# OpenBook_Schematic_v40.net
KiCad netlist of a schematic drawn in EAGLE
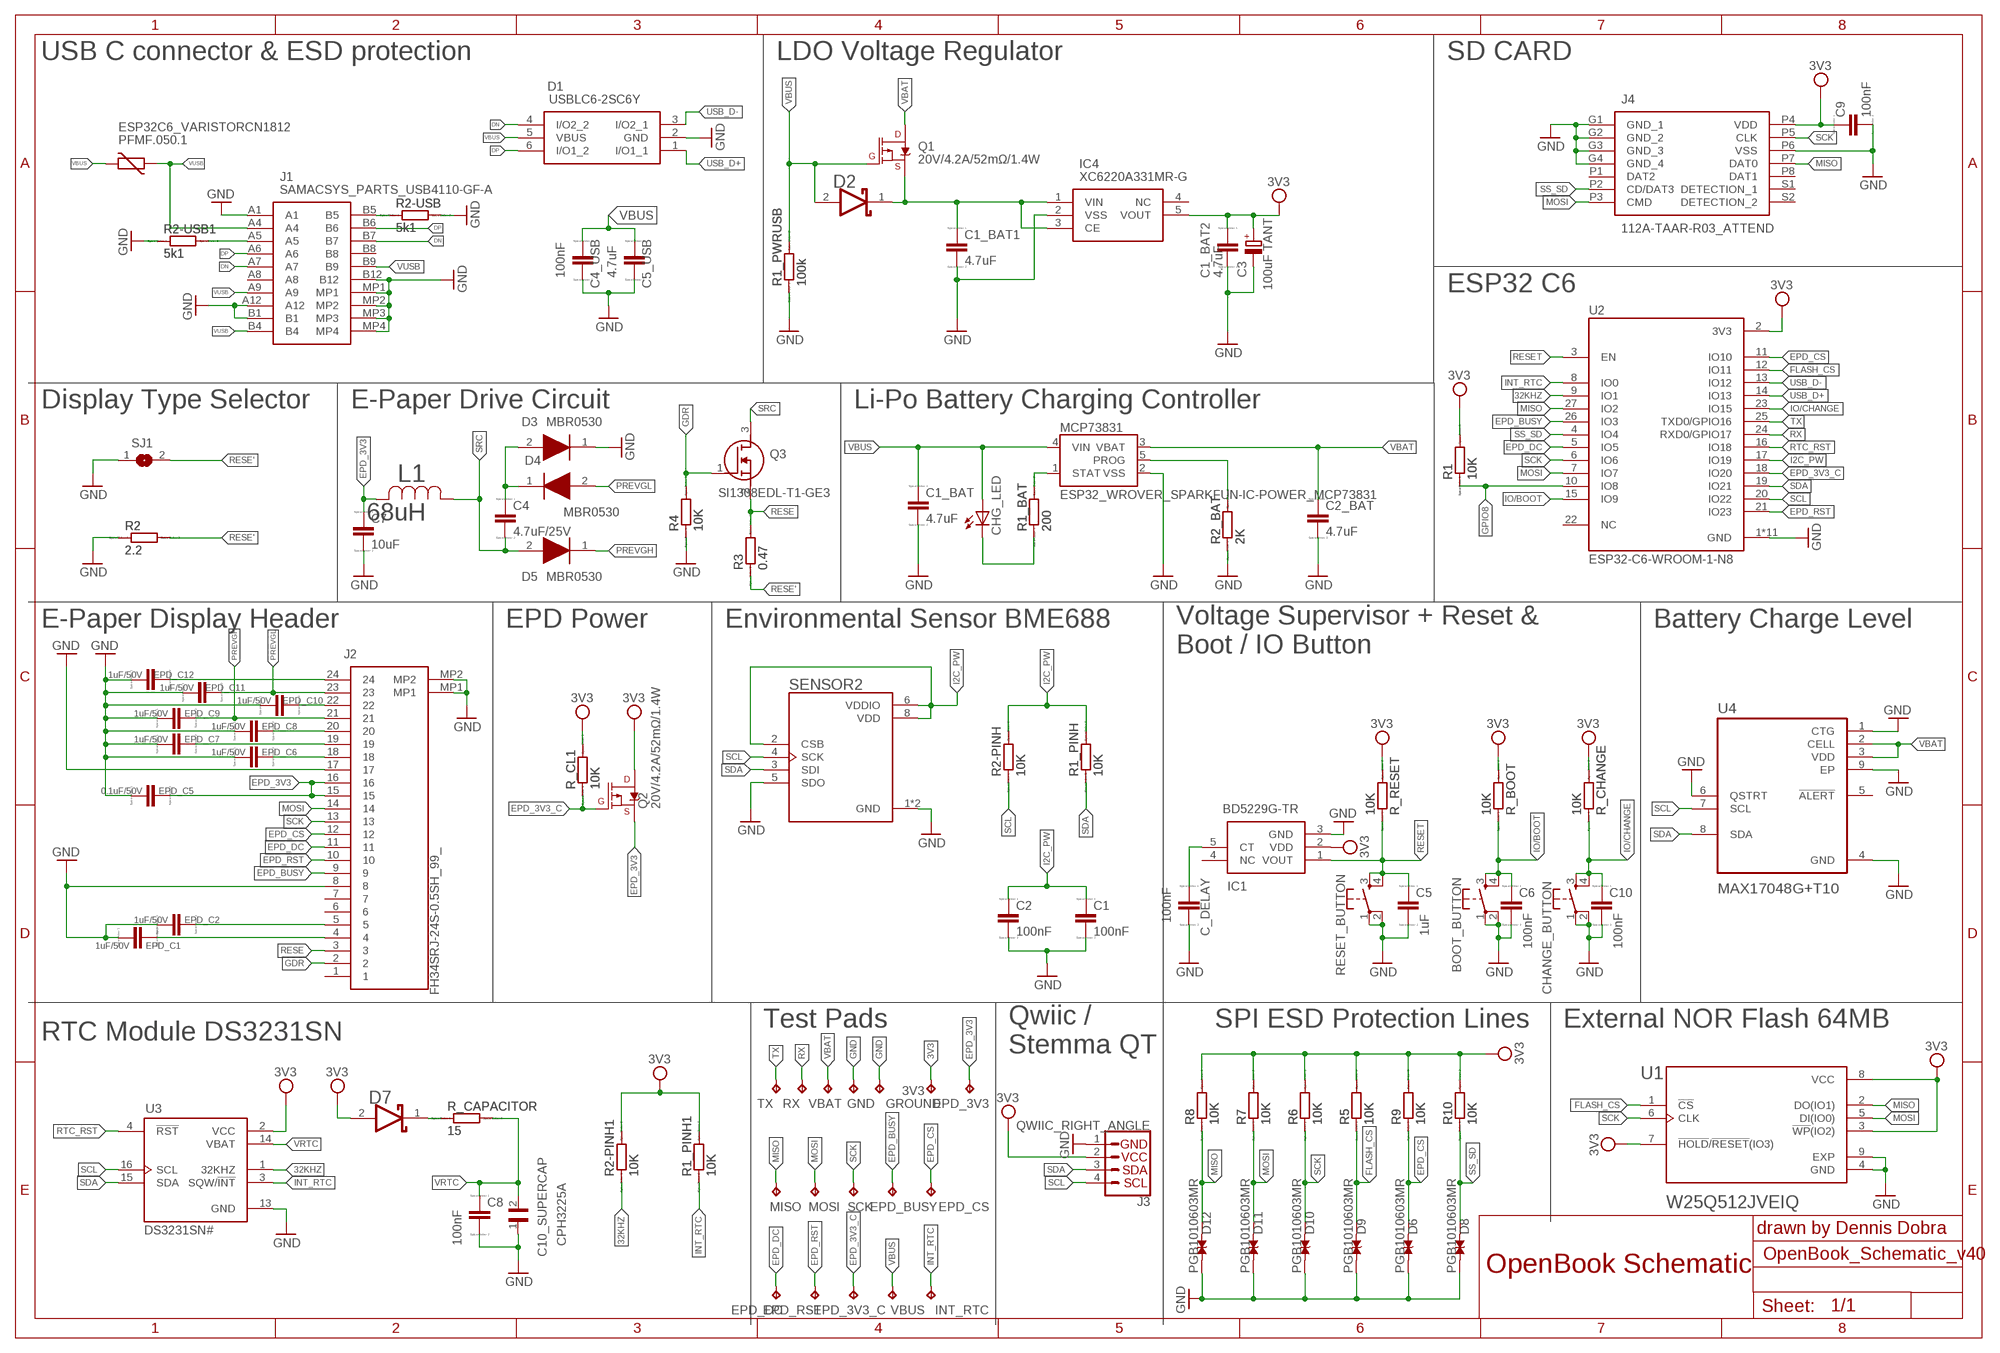
[diagram p0: schematic, sheet 1]

(export (version "E")
  (design (tool "Eeschema 10.0.6"))
  (components
    (comp (ref "3V3")
      (value "TPTP20R")
      (footprint "eagle-import:TP20R")
      (libsource (lib "eagle-import") (part "TPTP20R"))
    )
    (comp (ref "BOOT_BUTTON")
      (value "BUTTON_CUSYOMV1")
      (footprint "eagle-import:MYBUTTON")
      (libsource (lib "eagle-import") (part "BUTTON_CUSYOMV1"))
    )
    (comp (ref "C1")
      (value "100nF")
      (footprint "eagle-import:EAGLE-LTSPICE_C0402")
      (libsource (lib "eagle-import") (part "EAGLE-LTSPICE_CC0402"))
    )
    (comp (ref "C1_BAT")
      (value "4.7uF")
      (footprint "eagle-import:EAGLE-LTSPICE_C0402")
      (libsource (lib "eagle-import") (part "EAGLE-LTSPICE_CC0402"))
    )
    (comp (ref "C1_BAT1")
      (value "4.7uF")
      (footprint "eagle-import:EAGLE-LTSPICE_C0402")
      (libsource (lib "eagle-import") (part "EAGLE-LTSPICE_CC0402"))
    )
    (comp (ref "C1_BAT2")
      (value "4.7uF")
      (footprint "eagle-import:EAGLE-LTSPICE_C0402")
      (libsource (lib "eagle-import") (part "EAGLE-LTSPICE_CC0402"))
    )
    (comp (ref "C2")
      (value "100nF")
      (footprint "eagle-import:EAGLE-LTSPICE_C0402")
      (libsource (lib "eagle-import") (part "EAGLE-LTSPICE_CC0402"))
    )
    (comp (ref "C2_BAT")
      (value "4.7uF")
      (footprint "eagle-import:EAGLE-LTSPICE_C0402")
      (libsource (lib "eagle-import") (part "EAGLE-LTSPICE_CC0402"))
    )
    (comp (ref "C3")
      (value "100uF TANT")
      (footprint "eagle-import:RCL_CT3528")
      (libsource (lib "eagle-import") (part "RCL_CPOL-EUCT3528"))
    )
    (comp (ref "C4")
      (value "4.7uF/25V")
      (footprint "eagle-import:EAGLE-LTSPICE_C0402")
      (libsource (lib "eagle-import") (part "EAGLE-LTSPICE_CC0402"))
    )
    (comp (ref "C4_USB")
      (value "100nF")
      (footprint "eagle-import:EAGLE-LTSPICE_C0402")
      (libsource (lib "eagle-import") (part "EAGLE-LTSPICE_CC0402"))
    )
    (comp (ref "C5")
      (value "1uF")
      (footprint "eagle-import:EAGLE-LTSPICE_C0402")
      (libsource (lib "eagle-import") (part "EAGLE-LTSPICE_CC0402"))
    )
    (comp (ref "C5_USB")
      (value "4.7uF")
      (footprint "eagle-import:EAGLE-LTSPICE_C0402")
      (libsource (lib "eagle-import") (part "EAGLE-LTSPICE_CC0402"))
    )
    (comp (ref "C6")
      (value "100nF")
      (footprint "eagle-import:EAGLE-LTSPICE_C0402")
      (libsource (lib "eagle-import") (part "EAGLE-LTSPICE_CC0402"))
    )
    (comp (ref "C7")
      (value "10uF")
      (footprint "eagle-import:EAGLE-LTSPICE_C0402")
      (libsource (lib "eagle-import") (part "EAGLE-LTSPICE_CC0402"))
    )
    (comp (ref "C8")
      (value "100nF")
      (footprint "eagle-import:EAGLE-LTSPICE_C0402")
      (libsource (lib "eagle-import") (part "EAGLE-LTSPICE_CC0402"))
    )
    (comp (ref "C9")
      (value "100nF")
      (footprint "eagle-import:EAGLE-LTSPICE_C0402")
      (libsource (lib "eagle-import") (part "EAGLE-LTSPICE_CC0402"))
    )
    (comp (ref "C10")
      (value "100nF")
      (footprint "eagle-import:EAGLE-LTSPICE_C0402")
      (libsource (lib "eagle-import") (part "EAGLE-LTSPICE_CC0402"))
    )
    (comp (ref "C10_SUPERCAP")
      (value "CPH3225A")
      (footprint "eagle-import:CAPCP3225X100N")
      (fields (field (name "MF") "Seiko Instruments"))
      (libsource (lib "eagle-import") (part "CPH3225A"))
    )
    (comp (ref "CHANGE_BUTTON")
      (value "BUTTON_CUSYOMV1")
      (footprint "eagle-import:MYBUTTON")
      (libsource (lib "eagle-import") (part "BUTTON_CUSYOMV1"))
    )
    (comp (ref "CHG_LED")
      (value "ADAFRUIT_LEDCHIP-LED0603")
      (footprint "eagle-import:ADAFRUIT_CHIP-LED0603")
      (libsource (lib "eagle-import") (part "ADAFRUIT_LEDCHIP-LED0603"))
    )
    (comp (ref "C_DELAY")
      (value "100nF")
      (footprint "eagle-import:EAGLE-LTSPICE_C0402")
      (libsource (lib "eagle-import") (part "EAGLE-LTSPICE_CC0402"))
    )
    (comp (ref "D1")
      (value "USBLC6-2SC6Y")
      (footprint "eagle-import:SOT95P280X145-6N")
      (fields (field (name "MF") "STMicroelectronics"))
      (libsource (lib "eagle-import") (part "USBLC6-2SC6Y"))
    )
    (comp (ref "D2")
      (value "ESP32_WROVER_AVX---SD0805S020S1R0_AVX_SD0805S020S1R0_0_0AVX_SD0805S020S1R0_0_0")
      (footprint "eagle-import:ESP32_WROVER_AVX---SD0805S020S1R0_AVX_SD0805S020S1R0_0")
      (fields
        (field (name "DIGIKEY_PART_NUMBER") "478-7800-1-ND")
        (field (name "MF") "AVX")
        (field (name "MOUSER_PART_NUMBER") "581-SD0805S020S1R0")
      )
      (libsource (lib "eagle-import") (part "ESP32_WROVER_AVX---SD0805S020S1R0_AVX_SD0805S020S1R0_0_0AVX_SD0805S020S1R0_0_0"))
    )
    (comp (ref "D3")
      (value "MBR0530")
      (footprint "eagle-import:SOD3716X135N")
      (fields (field (name "MF") "ON Semiconductor"))
      (libsource (lib "eagle-import") (part "MBR0530"))
    )
    (comp (ref "D4")
      (value "MBR0530")
      (footprint "eagle-import:SOD3716X135N")
      (fields (field (name "MF") "ON Semiconductor"))
      (libsource (lib "eagle-import") (part "MBR0530"))
    )
    (comp (ref "D5")
      (value "MBR0530")
      (footprint "eagle-import:SOD3716X135N")
      (fields (field (name "MF") "ON Semiconductor"))
      (libsource (lib "eagle-import") (part "MBR0530"))
    )
    (comp (ref "D6")
      (value "PGB1010603MR")
      (footprint "eagle-import:DIOC1608X36N")
      (fields (field (name "MF") "Littelfuse Inc."))
      (libsource (lib "eagle-import") (part "PGB1010603MR"))
    )
    (comp (ref "D7")
      (value "ESP32_WROVER_AVX---SD0805S020S1R0_AVX_SD0805S020S1R0_0_0AVX_SD0805S020S1R0_0_0")
      (footprint "eagle-import:ESP32_WROVER_AVX---SD0805S020S1R0_AVX_SD0805S020S1R0_0")
      (fields
        (field (name "DIGIKEY_PART_NUMBER") "478-7800-1-ND")
        (field (name "MF") "AVX")
        (field (name "MOUSER_PART_NUMBER") "581-SD0805S020S1R0")
      )
      (libsource (lib "eagle-import") (part "ESP32_WROVER_AVX---SD0805S020S1R0_AVX_SD0805S020S1R0_0_0AVX_SD0805S020S1R0_0_0"))
    )
    (comp (ref "D8")
      (value "PGB1010603MR")
      (footprint "eagle-import:DIOC1608X36N")
      (fields (field (name "MF") "Littelfuse Inc."))
      (libsource (lib "eagle-import") (part "PGB1010603MR"))
    )
    (comp (ref "D9")
      (value "PGB1010603MR")
      (footprint "eagle-import:DIOC1608X36N")
      (fields (field (name "MF") "Littelfuse Inc."))
      (libsource (lib "eagle-import") (part "PGB1010603MR"))
    )
    (comp (ref "D10")
      (value "PGB1010603MR")
      (footprint "eagle-import:DIOC1608X36N")
      (fields (field (name "MF") "Littelfuse Inc."))
      (libsource (lib "eagle-import") (part "PGB1010603MR"))
    )
    (comp (ref "D11")
      (value "PGB1010603MR")
      (footprint "eagle-import:DIOC1608X36N")
      (fields (field (name "MF") "Littelfuse Inc."))
      (libsource (lib "eagle-import") (part "PGB1010603MR"))
    )
    (comp (ref "D12")
      (value "PGB1010603MR")
      (footprint "eagle-import:DIOC1608X36N")
      (fields (field (name "MF") "Littelfuse Inc."))
      (libsource (lib "eagle-import") (part "PGB1010603MR"))
    )
    (comp (ref "EPD_3V3")
      (value "TPTP20R")
      (footprint "eagle-import:TP20R")
      (libsource (lib "eagle-import") (part "TPTP20R"))
    )
    (comp (ref "EPD_3V3_C")
      (value "TPTP20R")
      (footprint "eagle-import:TP20R")
      (libsource (lib "eagle-import") (part "TPTP20R"))
    )
    (comp (ref "EPD_BUSY")
      (value "TPTP20R")
      (footprint "eagle-import:TP20R")
      (libsource (lib "eagle-import") (part "TPTP20R"))
    )
    (comp (ref "EPD_C1")
      (value "1uF/50V")
      (footprint "eagle-import:EAGLE-LTSPICE_C0402")
      (libsource (lib "eagle-import") (part "EAGLE-LTSPICE_CC0402"))
    )
    (comp (ref "EPD_C2")
      (value "1uF/50V")
      (footprint "eagle-import:EAGLE-LTSPICE_C0402")
      (libsource (lib "eagle-import") (part "EAGLE-LTSPICE_CC0402"))
    )
    (comp (ref "EPD_C5")
      (value "0.1uF/50V")
      (footprint "eagle-import:EAGLE-LTSPICE_C0402")
      (libsource (lib "eagle-import") (part "EAGLE-LTSPICE_CC0402"))
    )
    (comp (ref "EPD_C6")
      (value "1uF/50V")
      (footprint "eagle-import:EAGLE-LTSPICE_C0402")
      (libsource (lib "eagle-import") (part "EAGLE-LTSPICE_CC0402"))
    )
    (comp (ref "EPD_C7")
      (value "1uF/50V")
      (footprint "eagle-import:EAGLE-LTSPICE_C0402")
      (libsource (lib "eagle-import") (part "EAGLE-LTSPICE_CC0402"))
    )
    (comp (ref "EPD_C8")
      (value "1uF/50V")
      (footprint "eagle-import:EAGLE-LTSPICE_C0402")
      (libsource (lib "eagle-import") (part "EAGLE-LTSPICE_CC0402"))
    )
    (comp (ref "EPD_C9")
      (value "1uF/50V")
      (footprint "eagle-import:EAGLE-LTSPICE_C0402")
      (libsource (lib "eagle-import") (part "EAGLE-LTSPICE_CC0402"))
    )
    (comp (ref "EPD_C10")
      (value "1uF/50V")
      (footprint "eagle-import:EAGLE-LTSPICE_C0402")
      (libsource (lib "eagle-import") (part "EAGLE-LTSPICE_CC0402"))
    )
    (comp (ref "EPD_C11")
      (value "1uF/50V")
      (footprint "eagle-import:EAGLE-LTSPICE_C0402")
      (libsource (lib "eagle-import") (part "EAGLE-LTSPICE_CC0402"))
    )
    (comp (ref "EPD_C12")
      (value "1uF/50V")
      (footprint "eagle-import:EAGLE-LTSPICE_C0402")
      (libsource (lib "eagle-import") (part "EAGLE-LTSPICE_CC0402"))
    )
    (comp (ref "EPD_CS")
      (value "TPTP20R")
      (footprint "eagle-import:TP20R")
      (libsource (lib "eagle-import") (part "TPTP20R"))
    )
    (comp (ref "EPD_DC")
      (value "TPTP20R")
      (footprint "eagle-import:TP20R")
      (libsource (lib "eagle-import") (part "TPTP20R"))
    )
    (comp (ref "EPD_RST")
      (value "TPTP20R")
      (footprint "eagle-import:TP20R")
      (libsource (lib "eagle-import") (part "TPTP20R"))
    )
    (comp (ref "GND")
      (value "TPTP20R")
      (footprint "eagle-import:TP20R")
      (libsource (lib "eagle-import") (part "TPTP20R"))
    )
    (comp (ref "GROUND")
      (value "TPTP20R")
      (footprint "eagle-import:TP20R")
      (libsource (lib "eagle-import") (part "TPTP20R"))
    )
    (comp (ref "IC1")
      (value "BD5229G-TR")
      (footprint "eagle-import:SOT95P280X125-5N")
      (fields (field (name "MOUSER_PART_NUMBER") "755-BD5229G-TR"))
      (libsource (lib "eagle-import") (part "BD5229G-TR"))
    )
    (comp (ref "IC4")
      (value "XC6220A331MR-G")
      (footprint "eagle-import:SOT95P280X120-5N")
      (fields (field (name "MOUSER_PART_NUMBER") "865-XC6220A331MR-G"))
      (libsource (lib "eagle-import") (part "XC6220A331MR-G"))
    )
    (comp (ref "INT_RTC")
      (value "TPTP20R")
      (footprint "eagle-import:TP20R")
      (libsource (lib "eagle-import") (part "TPTP20R"))
    )
    (comp (ref "J1")
      (value "SAMACSYS_PARTS_USB4110-GF-A")
      (footprint "eagle-import:SAMACSYS_PARTS_USB4110GFA")
      (fields
        (field (name "MANUFACTURER_PART_NUMBER") "USB4110-GF-A")
        (field (name "MOUSER_PART_NUMBER") "640-USB4110-GF-A")
      )
      (libsource (lib "eagle-import") (part "SAMACSYS_PARTS_USB4110-GF-A"))
    )
    (comp (ref "J2")
      (value "FH34SRJ-24S-0.5SH_99_")
      (footprint "eagle-import:FH34SRJ24S05SH99")
      (fields
        (field (name "MANUFACTURER_PART_NUMBER") "FH34SRJ-24S-0.5SH(99)")
        (field (name "MOUSER_PART_NUMBER") "798-FH34SRJ24S05SH99")
      )
      (libsource (lib "eagle-import") (part "FH34SRJ-24S-0.5SH_99_"))
    )
    (comp (ref "J3")
      (value "QWIIC_RIGHT_ANGLE")
      (footprint "eagle-import:JST04_1MM_RA")
      (libsource (lib "eagle-import") (part "QWIIC_CONNECTORJS-1MM"))
    )
    (comp (ref "J4")
      (value "112A-TAAR-R03_ATTEND")
      (footprint "eagle-import:112ATAARR03ATTEND")
      (fields (field (name "MANUFACTURER_PART_NUMBER") "112A-TAAR-R03 ATTEND"))
      (libsource (lib "eagle-import") (part "112A-TAAR-R03_ATTEND"))
    )
    (comp (ref "L1")
      (value "68uH")
      (footprint "eagle-import:IND_4828-WE-TPC_WRE")
      (fields
        (field (name "MANUFACTURER_PART_NUMBER") "744043680")
        (field (name "COPYRIGHT") "Copyright (C) 2024 Ultra Librarian. All rights reserved.")
      )
      (libsource (lib "eagle-import") (part "744043680IND_4828-WE-TPC_WRE"))
    )
    (comp (ref "MCP73831")
      (value "ESP32_WROVER_SPARKFUN-IC-POWER_MCP73831")
      (footprint "eagle-import:ESP32_WROVER_SPARKFUN-IC-POWER_SOT23-5")
      (libsource (lib "eagle-import") (part "ESP32_WROVER_SPARKFUN-IC-POWER_MCP73831"))
    )
    (comp (ref "MISO")
      (value "TPTP20R")
      (footprint "eagle-import:TP20R")
      (libsource (lib "eagle-import") (part "TPTP20R"))
    )
    (comp (ref "MOSI")
      (value "TPTP20R")
      (footprint "eagle-import:TP20R")
      (libsource (lib "eagle-import") (part "TPTP20R"))
    )
    (comp (ref "PFMF.050.1")
      (value "ESP32C6_VARISTORCN1812")
      (footprint "eagle-import:ESP32C6_VARISTOR_CT_CN1812")
      (libsource (lib "eagle-import") (part "ESP32C6_VARISTORCN1812"))
    )
    (comp (ref "Q1")
      (value "20V/4.2A/52mΩ/1.4W")
      (footprint "eagle-import:ESP32_WROVER_SPARKFUN-DISCRETESEMI_SOT23-3")
      (libsource (lib "eagle-import") (part "ESP32_WROVER_SPARKFUN-DISCRETESEMI_MOSFET_PCH-DMG2305UX-7"))
    )
    (comp (ref "Q2")
      (value "20V/4.2A/52mΩ/1.4W")
      (footprint "eagle-import:ESP32_WROVER_SPARKFUN-DISCRETESEMI_SOT23-3")
      (libsource (lib "eagle-import") (part "ESP32_WROVER_SPARKFUN-DISCRETESEMI_MOSFET_PCH-DMG2305UX-7"))
    )
    (comp (ref "Q3")
      (value "SI1308EDL-T1-GE3")
      (footprint "eagle-import:SOT65P210X110-3N")
      (fields (field (name "MF") "Vishay Siliconix"))
      (libsource (lib "eagle-import") (part "SI1308EDL-T1-GE3"))
    )
    (comp (ref "R1")
      (value "10K")
      (footprint "eagle-import:ESP32_WROVER_EAGLE-LTSPICE_R0402")
      (libsource (lib "eagle-import") (part "ESP32_WROVER_EAGLE-LTSPICE_RR0402"))
    )
    (comp (ref "R1_BAT")
      (value "200")
      (footprint "eagle-import:ESP32_WROVER_EAGLE-LTSPICE_R0402")
      (libsource (lib "eagle-import") (part "ESP32_WROVER_EAGLE-LTSPICE_RR0402"))
    )
    (comp (ref "R1_PINH")
      (value "10K")
      (footprint "eagle-import:ESP32_WROVER_EAGLE-LTSPICE_R0402")
      (libsource (lib "eagle-import") (part "ESP32_WROVER_EAGLE-LTSPICE_RR0402"))
    )
    (comp (ref "R1_PINH1")
      (value "10K")
      (footprint "eagle-import:ESP32_WROVER_EAGLE-LTSPICE_R0402")
      (libsource (lib "eagle-import") (part "ESP32_WROVER_EAGLE-LTSPICE_RR0402"))
    )
    (comp (ref "R1_PWRUSB")
      (value "100k")
      (footprint "eagle-import:ESP32_WROVER_EAGLE-LTSPICE_R0402")
      (libsource (lib "eagle-import") (part "ESP32_WROVER_EAGLE-LTSPICE_RR0402"))
    )
    (comp (ref "R2")
      (value "2.2")
      (footprint "eagle-import:ESP32_WROVER_EAGLE-LTSPICE_R0402")
      (libsource (lib "eagle-import") (part "ESP32_WROVER_EAGLE-LTSPICE_RR0402"))
    )
    (comp (ref "R2-PINH")
      (value "10K")
      (footprint "eagle-import:ESP32_WROVER_EAGLE-LTSPICE_R0402")
      (libsource (lib "eagle-import") (part "ESP32_WROVER_EAGLE-LTSPICE_RR0402"))
    )
    (comp (ref "R2-PINH1")
      (value "10K")
      (footprint "eagle-import:ESP32_WROVER_EAGLE-LTSPICE_R0402")
      (libsource (lib "eagle-import") (part "ESP32_WROVER_EAGLE-LTSPICE_RR0402"))
    )
    (comp (ref "R2-USB")
      (value "5k1")
      (footprint "eagle-import:ESP32_WROVER_EAGLE-LTSPICE_R0402")
      (libsource (lib "eagle-import") (part "ESP32_WROVER_EAGLE-LTSPICE_RR0402"))
    )
    (comp (ref "R2-USB1")
      (value "5k1")
      (footprint "eagle-import:ESP32_WROVER_EAGLE-LTSPICE_R0402")
      (libsource (lib "eagle-import") (part "ESP32_WROVER_EAGLE-LTSPICE_RR0402"))
    )
    (comp (ref "R2_BAT")
      (value "2K")
      (footprint "eagle-import:ESP32_WROVER_EAGLE-LTSPICE_R0402")
      (libsource (lib "eagle-import") (part "ESP32_WROVER_EAGLE-LTSPICE_RR0402"))
    )
    (comp (ref "R3")
      (value "0.47")
      (footprint "eagle-import:ESP32_WROVER_EAGLE-LTSPICE_R0402")
      (libsource (lib "eagle-import") (part "ESP32_WROVER_EAGLE-LTSPICE_RR0402"))
    )
    (comp (ref "R4")
      (value "10K")
      (footprint "eagle-import:ESP32_WROVER_EAGLE-LTSPICE_R0402")
      (libsource (lib "eagle-import") (part "ESP32_WROVER_EAGLE-LTSPICE_RR0402"))
    )
    (comp (ref "R5")
      (value "10K")
      (footprint "eagle-import:ESP32_WROVER_EAGLE-LTSPICE_R0402")
      (libsource (lib "eagle-import") (part "ESP32_WROVER_EAGLE-LTSPICE_RR0402"))
    )
    (comp (ref "R6")
      (value "10K")
      (footprint "eagle-import:ESP32_WROVER_EAGLE-LTSPICE_R0402")
      (libsource (lib "eagle-import") (part "ESP32_WROVER_EAGLE-LTSPICE_RR0402"))
    )
    (comp (ref "R7")
      (value "10K")
      (footprint "eagle-import:ESP32_WROVER_EAGLE-LTSPICE_R0402")
      (libsource (lib "eagle-import") (part "ESP32_WROVER_EAGLE-LTSPICE_RR0402"))
    )
    (comp (ref "R8")
      (value "10K")
      (footprint "eagle-import:ESP32_WROVER_EAGLE-LTSPICE_R0402")
      (libsource (lib "eagle-import") (part "ESP32_WROVER_EAGLE-LTSPICE_RR0402"))
    )
    (comp (ref "R9")
      (value "10K")
      (footprint "eagle-import:ESP32_WROVER_EAGLE-LTSPICE_R0402")
      (libsource (lib "eagle-import") (part "ESP32_WROVER_EAGLE-LTSPICE_RR0402"))
    )
    (comp (ref "R10")
      (value "10K")
      (footprint "eagle-import:ESP32_WROVER_EAGLE-LTSPICE_R0402")
      (libsource (lib "eagle-import") (part "ESP32_WROVER_EAGLE-LTSPICE_RR0402"))
    )
    (comp (ref "RESET_BUTTON")
      (value "BUTTON_CUSYOMV1")
      (footprint "eagle-import:MYBUTTON")
      (libsource (lib "eagle-import") (part "BUTTON_CUSYOMV1"))
    )
    (comp (ref "RX")
      (value "TPTP20R")
      (footprint "eagle-import:TP20R")
      (libsource (lib "eagle-import") (part "TPTP20R"))
    )
    (comp (ref "R_BOOT")
      (value "10K")
      (footprint "eagle-import:ESP32_WROVER_EAGLE-LTSPICE_R0402")
      (libsource (lib "eagle-import") (part "ESP32_WROVER_EAGLE-LTSPICE_RR0402"))
    )
    (comp (ref "R_CAPACITOR")
      (value "15")
      (footprint "eagle-import:ESP32_WROVER_EAGLE-LTSPICE_R0402")
      (libsource (lib "eagle-import") (part "ESP32_WROVER_EAGLE-LTSPICE_RR0402"))
    )
    (comp (ref "R_CHANGE")
      (value "10K")
      (footprint "eagle-import:ESP32_WROVER_EAGLE-LTSPICE_R0402")
      (libsource (lib "eagle-import") (part "ESP32_WROVER_EAGLE-LTSPICE_RR0402"))
    )
    (comp (ref "R_CL1")
      (value "10K")
      (footprint "eagle-import:ESP32_WROVER_EAGLE-LTSPICE_R0402")
      (libsource (lib "eagle-import") (part "ESP32_WROVER_EAGLE-LTSPICE_RR0402"))
    )
    (comp (ref "R_RESET")
      (value "10K")
      (footprint "eagle-import:ESP32_WROVER_EAGLE-LTSPICE_R0402")
      (libsource (lib "eagle-import") (part "ESP32_WROVER_EAGLE-LTSPICE_RR0402"))
    )
    (comp (ref "SCK")
      (value "TPTP20R")
      (footprint "eagle-import:TP20R")
      (libsource (lib "eagle-import") (part "TPTP20R"))
    )
    (comp (ref "SENSOR2")
      (value "ESP32_WROVER_BME680_BME680")
      (footprint "eagle-import:ESP32_WROVER_BME680_PSON80P300X300X100-8N")
      (fields (field (name "MF") "Bosch Sensortec") (field (name "MP") "BME680"))
      (libsource (lib "eagle-import") (part "ESP32_WROVER_BME680_BME680"))
    )
    (comp (ref "SJ1") (value "SJ") (footprint "eagle-import:SJ") (libsource (lib "eagle-import") (part "SJ")))
    (comp (ref "TX")
      (value "TPTP20R")
      (footprint "eagle-import:TP20R")
      (libsource (lib "eagle-import") (part "TPTP20R"))
    )
    (comp (ref "U1")
      (value "W25Q512JVEIQ")
      (footprint "eagle-import:SON127P600X800X80-9N")
      (fields (field (name "MF") "Winbond Electronics"))
      (libsource (lib "eagle-import") (part "W25Q512JVEIQ"))
    )
    (comp (ref "U2")
      (value "ESP32-C6-WROOM-1-N8")
      (footprint "eagle-import:XCVR_ESP32-C6-WROOM-1-N8")
      (fields (field (name "MF") "Espressif Systems"))
      (libsource (lib "eagle-import") (part "ESP32-C6-WROOM-1-N8"))
    )
    (comp (ref "U3")
      (value "DS3231SN#")
      (footprint "eagle-import:SOIC127P1032X265-16N")
      (fields (field (name "MF") "Analog Devices"))
      (libsource (lib "eagle-import") (part "DS3231SN#"))
    )
    (comp (ref "U4")
      (value "MAX17048G+T10")
      (footprint "eagle-import:SON50P200X200X80-9N")
      (fields (field (name "MF") "Analog Devices"))
      (libsource (lib "eagle-import") (part "MAX17048G+T10"))
    )
    (comp (ref "VBAT")
      (value "TPTP20R")
      (footprint "eagle-import:TP20R")
      (libsource (lib "eagle-import") (part "TPTP20R"))
    )
    (comp (ref "VBUS")
      (value "TPTP20R")
      (footprint "eagle-import:TP20R")
      (libsource (lib "eagle-import") (part "TPTP20R"))
    )
  )
  (nets
    (net (code "1") (name "3V3") (class "Default")
      (node (ref "3V3") (pin "TP") (pinfunction "TP_TP") (pintype "input"))
      (node (ref "C1_BAT2") (pin "1") (pinfunction "1_1") (pintype "passive"))
      (node (ref "C3") (pin "+") (pinfunction "+_+") (pintype "passive"))
      (node (ref "C9") (pin "1") (pinfunction "1_1") (pintype "passive"))
      (node (ref "D7") (pin "2") (pinfunction "ANODE_2") (pintype "bidirectional"))
      (node (ref "IC1") (pin "2") (pinfunction "VDD_2") (pintype "bidirectional"))
      (node (ref "IC4") (pin "5") (pinfunction "VOUT_5") (pintype "bidirectional"))
      (node (ref "J3") (pin "2") (pinfunction "2_2") (pintype "power_in"))
      (node (ref "J4") (pin "P4") (pinfunction "VDD_P4") (pintype "bidirectional"))
      (node (ref "Q2") (pin "3") (pinfunction "D_3") (pintype "bidirectional"))
      (node (ref "R1") (pin "2") (pinfunction "2_2") (pintype "passive"))
      (node (ref "R10") (pin "2") (pinfunction "2_2") (pintype "passive"))
      (node (ref "R1_PINH1") (pin "2") (pinfunction "2_2") (pintype "passive"))
      (node (ref "R2-PINH1") (pin "2") (pinfunction "2_2") (pintype "passive"))
      (node (ref "R5") (pin "2") (pinfunction "2_2") (pintype "passive"))
      (node (ref "R6") (pin "2") (pinfunction "2_2") (pintype "passive"))
      (node (ref "R7") (pin "2") (pinfunction "2_2") (pintype "passive"))
      (node (ref "R8") (pin "2") (pinfunction "2_2") (pintype "passive"))
      (node (ref "R9") (pin "2") (pinfunction "2_2") (pintype "passive"))
      (node (ref "R_BOOT") (pin "2") (pinfunction "2_2") (pintype "passive"))
      (node (ref "R_CHANGE") (pin "2") (pinfunction "2_2") (pintype "passive"))
      (node (ref "R_CL1") (pin "2") (pinfunction "2_2") (pintype "passive"))
      (node (ref "R_RESET") (pin "2") (pinfunction "2_2") (pintype "passive"))
      (node (ref "U1") (pin "3") (pinfunction "~{WP}(IO2)_3") (pintype "bidirectional"))
      (node (ref "U1") (pin "7") (pinfunction "~{HOLD}/~{RESET}(IO3)_7") (pintype "bidirectional"))
      (node (ref "U1") (pin "8") (pinfunction "VCC_8") (pintype "power_in"))
      (node (ref "U2") (pin "2") (pinfunction "3V3_2") (pintype "power_in"))
      (node (ref "U3") (pin "2") (pinfunction "VCC_2") (pintype "power_in"))
    )
    (net (code "2") (name "32KHZ") (class "Default")
      (node (ref "R2-PINH1") (pin "1") (pinfunction "1_1") (pintype "passive"))
      (node (ref "U2") (pin "9") (pinfunction "IO1_9") (pintype "bidirectional"))
      (node (ref "U3") (pin "1") (pinfunction "32KHZ_1") (pintype "output"))
    )
    (net (code "3") (name "DN") (class "Default")
      (node (ref "D1") (pin "4") (pinfunction "I/O2_2_4") (pintype "bidirectional"))
      (node (ref "J1") (pin "A7") (pinfunction "A7_A7") (pintype "bidirectional"))
      (node (ref "J1") (pin "B7") (pinfunction "B7_B7") (pintype "bidirectional"))
    )
    (net (code "4") (name "DP") (class "Default")
      (node (ref "D1") (pin "6") (pinfunction "I/O1_2_6") (pintype "bidirectional"))
      (node (ref "J1") (pin "A6") (pinfunction "A6_A6") (pintype "bidirectional"))
      (node (ref "J1") (pin "B6") (pinfunction "B6_B6") (pintype "bidirectional"))
    )
    (net (code "5") (name "EPD_3V3") (class "Default")
      (node (ref "C7") (pin "1") (pinfunction "1_1") (pintype "passive"))
      (node (ref "EPD_3V3") (pin "TP") (pinfunction "TP_TP") (pintype "input"))
      (node (ref "EPD_C5") (pin "2") (pinfunction "2_2") (pintype "passive"))
      (node (ref "J2") (pin "15") (pinfunction "15_15") (pintype "bidirectional"))
      (node (ref "J2") (pin "16") (pinfunction "16_16") (pintype "bidirectional"))
      (node (ref "L1") (pin "2") (pinfunction "2_2") (pintype "passive"))
      (node (ref "Q2") (pin "2") (pinfunction "S_2") (pintype "bidirectional"))
    )
    (net (code "6") (name "EPD_3V3_C") (class "Default")
      (node (ref "EPD_3V3_C") (pin "TP") (pinfunction "TP_TP") (pintype "input"))
      (node (ref "Q2") (pin "1") (pinfunction "G_1") (pintype "bidirectional"))
      (node (ref "R_CL1") (pin "1") (pinfunction "1_1") (pintype "passive"))
      (node (ref "U2") (pin "18") (pinfunction "IO20_18") (pintype "bidirectional"))
    )
    (net (code "7") (name "EPD_BUSY") (class "Default")
      (node (ref "EPD_BUSY") (pin "TP") (pinfunction "TP_TP") (pintype "input"))
      (node (ref "J2") (pin "9") (pinfunction "9_9") (pintype "bidirectional"))
      (node (ref "U2") (pin "26") (pinfunction "IO3_26") (pintype "bidirectional"))
    )
    (net (code "8") (name "EPD_CS") (class "Default")
      (node (ref "D6") (pin "2") (pinfunction "2_2") (pintype "passive"))
      (node (ref "EPD_CS") (pin "TP") (pinfunction "TP_TP") (pintype "input"))
      (node (ref "J2") (pin "12") (pinfunction "12_12") (pintype "bidirectional"))
      (node (ref "R9") (pin "1") (pinfunction "1_1") (pintype "passive"))
      (node (ref "U2") (pin "11") (pinfunction "IO10_11") (pintype "bidirectional"))
    )
    (net (code "9") (name "EPD_DC") (class "Default")
      (node (ref "EPD_DC") (pin "TP") (pinfunction "TP_TP") (pintype "input"))
      (node (ref "J2") (pin "11") (pinfunction "11_11") (pintype "bidirectional"))
      (node (ref "U2") (pin "5") (pinfunction "IO5_5") (pintype "bidirectional"))
    )
    (net (code "10") (name "EPD_RST") (class "Default")
      (node (ref "EPD_RST") (pin "TP") (pinfunction "TP_TP") (pintype "input"))
      (node (ref "J2") (pin "10") (pinfunction "10_10") (pintype "bidirectional"))
      (node (ref "U2") (pin "21") (pinfunction "IO23_21") (pintype "bidirectional"))
    )
    (net (code "11") (name "FLASH_CS") (class "Default")
      (node (ref "D9") (pin "2") (pinfunction "2_2") (pintype "passive"))
      (node (ref "R5") (pin "1") (pinfunction "1_1") (pintype "passive"))
      (node (ref "U1") (pin "1") (pinfunction "~{CS}_1") (pintype "input"))
      (node (ref "U2") (pin "12") (pinfunction "IO11_12") (pintype "bidirectional"))
    )
    (net (code "12") (name "GDR") (class "Default")
      (node (ref "J2") (pin "2") (pinfunction "2_2") (pintype "bidirectional"))
      (node (ref "Q3") (pin "1") (pinfunction "G_1") (pintype "bidirectional"))
      (node (ref "R4") (pin "2") (pinfunction "2_2") (pintype "passive"))
    )
    (net (code "13") (name "GND") (class "Default")
      (node (ref "BOOT_BUTTON") (pin "1") (pinfunction "1_1") (pintype "passive"))
      (node (ref "BOOT_BUTTON") (pin "2") (pinfunction "2_2") (pintype "passive"))
      (node (ref "C1") (pin "2") (pinfunction "2_2") (pintype "passive"))
      (node (ref "C10") (pin "2") (pinfunction "2_2") (pintype "passive"))
      (node (ref "C10_SUPERCAP") (pin "1") (pinfunction "1_1") (pintype "passive"))
      (node (ref "C1_BAT") (pin "2") (pinfunction "2_2") (pintype "passive"))
      (node (ref "C1_BAT1") (pin "2") (pinfunction "2_2") (pintype "passive"))
      (node (ref "C1_BAT2") (pin "2") (pinfunction "2_2") (pintype "passive"))
      (node (ref "C2") (pin "2") (pinfunction "2_2") (pintype "passive"))
      (node (ref "C2_BAT") (pin "2") (pinfunction "2_2") (pintype "passive"))
      (node (ref "C3") (pin "-") (pinfunction "-_-") (pintype "passive"))
      (node (ref "C4_USB") (pin "2") (pinfunction "2_2") (pintype "passive"))
      (node (ref "C5") (pin "2") (pinfunction "2_2") (pintype "passive"))
      (node (ref "C5_USB") (pin "2") (pinfunction "2_2") (pintype "passive"))
      (node (ref "C6") (pin "2") (pinfunction "2_2") (pintype "passive"))
      (node (ref "C7") (pin "2") (pinfunction "2_2") (pintype "passive"))
      (node (ref "C8") (pin "2") (pinfunction "2_2") (pintype "passive"))
      (node (ref "C9") (pin "2") (pinfunction "2_2") (pintype "passive"))
      (node (ref "CHANGE_BUTTON") (pin "1") (pinfunction "1_1") (pintype "passive"))
      (node (ref "CHANGE_BUTTON") (pin "2") (pinfunction "2_2") (pintype "passive"))
      (node (ref "C_DELAY") (pin "2") (pinfunction "2_2") (pintype "passive"))
      (node (ref "D1") (pin "2") (pinfunction "GND_2") (pintype "bidirectional"))
      (node (ref "D10") (pin "1") (pinfunction "1_1") (pintype "passive"))
      (node (ref "D11") (pin "1") (pinfunction "1_1") (pintype "passive"))
      (node (ref "D12") (pin "1") (pinfunction "1_1") (pintype "passive"))
      (node (ref "D3") (pin "1") (pinfunction "K_1") (pintype "bidirectional"))
      (node (ref "D6") (pin "1") (pinfunction "1_1") (pintype "passive"))
      (node (ref "D8") (pin "1") (pinfunction "1_1") (pintype "passive"))
      (node (ref "D9") (pin "1") (pinfunction "1_1") (pintype "passive"))
      (node (ref "EPD_C1") (pin "1") (pinfunction "1_1") (pintype "passive"))
      (node (ref "EPD_C10") (pin "1") (pinfunction "1_1") (pintype "passive"))
      (node (ref "EPD_C11") (pin "1") (pinfunction "1_1") (pintype "passive"))
      (node (ref "EPD_C12") (pin "1") (pinfunction "1_1") (pintype "passive"))
      (node (ref "EPD_C2") (pin "1") (pinfunction "1_1") (pintype "passive"))
      (node (ref "EPD_C5") (pin "1") (pinfunction "1_1") (pintype "passive"))
      (node (ref "EPD_C6") (pin "1") (pinfunction "1_1") (pintype "passive"))
      (node (ref "EPD_C7") (pin "1") (pinfunction "1_1") (pintype "passive"))
      (node (ref "EPD_C8") (pin "1") (pinfunction "1_1") (pintype "passive"))
      (node (ref "EPD_C9") (pin "1") (pinfunction "1_1") (pintype "passive"))
      (node (ref "GND") (pin "TP") (pinfunction "TP_TP") (pintype "input"))
      (node (ref "GROUND") (pin "TP") (pinfunction "TP_TP") (pintype "input"))
      (node (ref "IC1") (pin "3") (pinfunction "GND_3") (pintype "bidirectional"))
      (node (ref "IC4") (pin "2") (pinfunction "VSS_2") (pintype "bidirectional"))
      (node (ref "J1") (pin "A1") (pinfunction "A1_A1") (pintype "bidirectional"))
      (node (ref "J1") (pin "A12") (pinfunction "A12_A12") (pintype "bidirectional"))
      (node (ref "J1") (pin "B1") (pinfunction "B1_B1") (pintype "bidirectional"))
      (node (ref "J1") (pin "B12") (pinfunction "B12_B12") (pintype "bidirectional"))
      (node (ref "J1") (pin "MP1") (pinfunction "MP1_MP1") (pintype "bidirectional"))
      (node (ref "J1") (pin "MP2") (pinfunction "MP2_MP2") (pintype "bidirectional"))
      (node (ref "J1") (pin "MP3") (pinfunction "MP3_MP3") (pintype "bidirectional"))
      (node (ref "J1") (pin "MP4") (pinfunction "MP4_MP4") (pintype "bidirectional"))
      (node (ref "J2") (pin "17") (pinfunction "17_17") (pintype "bidirectional"))
      (node (ref "J2") (pin "8") (pinfunction "8_8") (pintype "bidirectional"))
      (node (ref "J2") (pin "MP1") (pinfunction "MP1_MP1") (pintype "bidirectional"))
      (node (ref "J2") (pin "MP2") (pinfunction "MP2_MP2") (pintype "bidirectional"))
      (node (ref "J3") (pin "1") (pinfunction "1_1") (pintype "power_in"))
      (node (ref "J4") (pin "G1") (pinfunction "GND_1_G1") (pintype "bidirectional"))
      (node (ref "J4") (pin "G2") (pinfunction "GND_2_G2") (pintype "bidirectional"))
      (node (ref "J4") (pin "G3") (pinfunction "GND_3_G3") (pintype "bidirectional"))
      (node (ref "J4") (pin "G4") (pinfunction "GND_4_G4") (pintype "bidirectional"))
      (node (ref "J4") (pin "P6") (pinfunction "VSS_P6") (pintype "bidirectional"))
      (node (ref "MCP73831") (pin "2") (pinfunction "VSS_2") (pintype "power_in"))
      (node (ref "R1_PWRUSB") (pin "1") (pinfunction "1_1") (pintype "passive"))
      (node (ref "R2") (pin "1") (pinfunction "1_1") (pintype "passive"))
      (node (ref "R2-USB") (pin "2") (pinfunction "2_2") (pintype "passive"))
      (node (ref "R2-USB1") (pin "1") (pinfunction "1_1") (pintype "passive"))
      (node (ref "R2_BAT") (pin "1") (pinfunction "1_1") (pintype "passive"))
      (node (ref "R4") (pin "1") (pinfunction "1_1") (pintype "passive"))
      (node (ref "RESET_BUTTON") (pin "1") (pinfunction "1_1") (pintype "passive"))
      (node (ref "RESET_BUTTON") (pin "2") (pinfunction "2_2") (pintype "passive"))
      (node (ref "SENSOR2") (pin "1") (pinfunction "GND_1") (pintype "power_in"))
      (node (ref "SENSOR2") (pin "5") (pinfunction "SDO_5") (pintype "bidirectional"))
      (node (ref "SENSOR2") (pin "7") (pinfunction "GND_7") (pintype "power_in"))
      (node (ref "SJ1") (pin "1") (pinfunction "1_1") (pintype "passive"))
      (node (ref "U1") (pin "4") (pinfunction "GND_4") (pintype "power_in"))
      (node (ref "U1") (pin "9") (pinfunction "EXP_9") (pintype "passive"))
      (node (ref "U2") (pin "1") (pinfunction "GND_1") (pintype "power_in"))
      (node (ref "U2") (pin "28") (pinfunction "GND_28") (pintype "power_in"))
      (node (ref "U2") (pin "29_1") (pinfunction "GND_29_1") (pintype "power_in"))
      (node (ref "U2") (pin "29_2") (pinfunction "GND_29_2") (pintype "power_in"))
      (node (ref "U2") (pin "29_3") (pinfunction "GND_29_3") (pintype "power_in"))
      (node (ref "U2") (pin "29_4") (pinfunction "GND_29_4") (pintype "power_in"))
      (node (ref "U2") (pin "29_5") (pinfunction "GND_29_5") (pintype "power_in"))
      (node (ref "U2") (pin "29_6") (pinfunction "GND_29_6") (pintype "power_in"))
      (node (ref "U2") (pin "29_7") (pinfunction "GND_29_7") (pintype "power_in"))
      (node (ref "U2") (pin "29_8") (pinfunction "GND_29_8") (pintype "power_in"))
      (node (ref "U2") (pin "29_9") (pinfunction "GND_29_9") (pintype "power_in"))
      (node (ref "U3") (pin "13") (pinfunction "GND_13") (pintype "power_in"))
      (node (ref "U4") (pin "1") (pinfunction "CTG_1") (pintype "power_in"))
      (node (ref "U4") (pin "4") (pinfunction "GND_4") (pintype "power_in"))
      (node (ref "U4") (pin "6") (pinfunction "QSTRT_6") (pintype "input"))
      (node (ref "U4") (pin "9") (pinfunction "EP_9") (pintype "power_in"))
    )
    (net (code "14") (name "GPIO8") (class "Default")
      (node (ref "R1") (pin "1") (pinfunction "1_1") (pintype "passive"))
      (node (ref "U2") (pin "10") (pinfunction "IO8_10") (pintype "bidirectional"))
    )
    (net (code "15") (name "I2C_PW") (class "Default")
      (node (ref "C1") (pin "1") (pinfunction "1_1") (pintype "passive"))
      (node (ref "C2") (pin "1") (pinfunction "1_1") (pintype "passive"))
      (node (ref "R1_PINH") (pin "2") (pinfunction "2_2") (pintype "passive"))
      (node (ref "R2-PINH") (pin "2") (pinfunction "2_2") (pintype "passive"))
      (node (ref "SENSOR2") (pin "2") (pinfunction "CSB_2") (pintype "input"))
      (node (ref "SENSOR2") (pin "6") (pinfunction "VDDIO_6") (pintype "power_in"))
      (node (ref "SENSOR2") (pin "8") (pinfunction "VDD_8") (pintype "power_in"))
      (node (ref "U2") (pin "17") (pinfunction "IO19_17") (pintype "bidirectional"))
    )
    (net (code "16") (name "INT_RTC") (class "Default")
      (node (ref "INT_RTC") (pin "TP") (pinfunction "TP_TP") (pintype "input"))
      (node (ref "R1_PINH1") (pin "1") (pinfunction "1_1") (pintype "passive"))
      (node (ref "U2") (pin "8") (pinfunction "IO0_8") (pintype "bidirectional"))
      (node (ref "U3") (pin "3") (pinfunction "SQW/~{INT}_3") (pintype "output"))
    )
    (net (code "17") (name "IO{slash}BOOT") (class "Default")
      (node (ref "BOOT_BUTTON") (pin "3") (pinfunction "3_3") (pintype "passive"))
      (node (ref "BOOT_BUTTON") (pin "4") (pinfunction "4_4") (pintype "passive"))
      (node (ref "C6") (pin "1") (pinfunction "1_1") (pintype "passive"))
      (node (ref "R_BOOT") (pin "1") (pinfunction "1_1") (pintype "passive"))
      (node (ref "U2") (pin "15") (pinfunction "IO9_15") (pintype "bidirectional"))
    )
    (net (code "18") (name "IO{slash}CHANGE") (class "Default")
      (node (ref "C10") (pin "1") (pinfunction "1_1") (pintype "passive"))
      (node (ref "CHANGE_BUTTON") (pin "3") (pinfunction "3_3") (pintype "passive"))
      (node (ref "CHANGE_BUTTON") (pin "4") (pinfunction "4_4") (pintype "passive"))
      (node (ref "R_CHANGE") (pin "1") (pinfunction "1_1") (pintype "passive"))
      (node (ref "U2") (pin "23") (pinfunction "IO15_23") (pintype "bidirectional"))
    )
    (net (code "19") (name "MISO") (class "Default")
      (node (ref "D12") (pin "2") (pinfunction "2_2") (pintype "passive"))
      (node (ref "J4") (pin "P7") (pinfunction "DAT0_P7") (pintype "bidirectional"))
      (node (ref "MISO") (pin "TP") (pinfunction "TP_TP") (pintype "input"))
      (node (ref "R8") (pin "1") (pinfunction "1_1") (pintype "passive"))
      (node (ref "U1") (pin "2") (pinfunction "DO(IO1)_2") (pintype "bidirectional"))
      (node (ref "U2") (pin "27") (pinfunction "IO2_27") (pintype "bidirectional"))
    )
    (net (code "20") (name "MOSI") (class "Default")
      (node (ref "D11") (pin "2") (pinfunction "2_2") (pintype "passive"))
      (node (ref "J2") (pin "14") (pinfunction "14_14") (pintype "bidirectional"))
      (node (ref "J4") (pin "P3") (pinfunction "CMD_P3") (pintype "bidirectional"))
      (node (ref "MOSI") (pin "TP") (pinfunction "TP_TP") (pintype "input"))
      (node (ref "R7") (pin "1") (pinfunction "1_1") (pintype "passive"))
      (node (ref "U1") (pin "5") (pinfunction "DI(IO0)_5") (pintype "bidirectional"))
      (node (ref "U2") (pin "7") (pinfunction "IO7_7") (pintype "bidirectional"))
    )
    (net (code "21") (name "Net-(CHG_LED-PadC)") (class "Default")
      (node (ref "CHG_LED") (pin "C") (pinfunction "C_C") (pintype "passive"))
      (node (ref "R1_BAT") (pin "1") (pinfunction "1_1") (pintype "passive"))
    )
    (net (code "22") (name "Net-(D2-CATHODE)") (class "Default")
      (node (ref "C1_BAT1") (pin "1") (pinfunction "1_1") (pintype "passive"))
      (node (ref "D2") (pin "1") (pinfunction "CATHODE_1") (pintype "bidirectional"))
      (node (ref "IC4") (pin "1") (pinfunction "VIN_1") (pintype "bidirectional"))
      (node (ref "IC4") (pin "3") (pinfunction "CE_3") (pintype "bidirectional"))
      (node (ref "Q1") (pin "2") (pinfunction "S_2") (pintype "bidirectional"))
    )
    (net (code "23") (name "Net-(D3-A)") (class "Default")
      (node (ref "C4") (pin "1") (pinfunction "1_1") (pintype "passive"))
      (node (ref "D3") (pin "2") (pinfunction "A_2") (pintype "bidirectional"))
      (node (ref "D4") (pin "1") (pinfunction "K_1") (pintype "bidirectional"))
    )
    (net (code "24") (name "Net-(D7-CATHODE)") (class "Default")
      (node (ref "D7") (pin "1") (pinfunction "CATHODE_1") (pintype "bidirectional"))
      (node (ref "R_CAPACITOR") (pin "1") (pinfunction "1_1") (pintype "passive"))
    )
    (net (code "25") (name "Net-(EPD_C1-Pad2)") (class "Default")
      (node (ref "EPD_C1") (pin "2") (pinfunction "2_2") (pintype "passive"))
      (node (ref "J2") (pin "4") (pinfunction "4_4") (pintype "bidirectional"))
    )
    (net (code "26") (name "Net-(EPD_C2-Pad2)") (class "Default")
      (node (ref "EPD_C2") (pin "2") (pinfunction "2_2") (pintype "passive"))
      (node (ref "J2") (pin "5") (pinfunction "5_5") (pintype "bidirectional"))
    )
    (net (code "27") (name "Net-(EPD_C6-Pad2)") (class "Default")
      (node (ref "EPD_C6") (pin "2") (pinfunction "2_2") (pintype "passive"))
      (node (ref "J2") (pin "18") (pinfunction "18_18") (pintype "bidirectional"))
    )
    (net (code "28") (name "Net-(EPD_C7-Pad2)") (class "Default")
      (node (ref "EPD_C7") (pin "2") (pinfunction "2_2") (pintype "passive"))
      (node (ref "J2") (pin "19") (pinfunction "19_19") (pintype "bidirectional"))
    )
    (net (code "29") (name "Net-(EPD_C8-Pad2)") (class "Default")
      (node (ref "EPD_C8") (pin "2") (pinfunction "2_2") (pintype "passive"))
      (node (ref "J2") (pin "20") (pinfunction "20_20") (pintype "bidirectional"))
    )
    (net (code "30") (name "Net-(EPD_C10-Pad2)") (class "Default")
      (node (ref "EPD_C10") (pin "2") (pinfunction "2_2") (pintype "passive"))
      (node (ref "J2") (pin "22") (pinfunction "22_22") (pintype "bidirectional"))
    )
    (net (code "31") (name "Net-(EPD_C12-Pad2)") (class "Default")
      (node (ref "EPD_C12") (pin "2") (pinfunction "2_2") (pintype "passive"))
      (node (ref "J2") (pin "24") (pinfunction "24_24") (pintype "bidirectional"))
    )
    (net (code "32") (name "Net-(IC1-CT)") (class "Default")
      (node (ref "C_DELAY") (pin "1") (pinfunction "1_1") (pintype "passive"))
      (node (ref "IC1") (pin "5") (pinfunction "CT_5") (pintype "bidirectional"))
    )
    (net (code "33") (name "Net-(J1-PadA5)") (class "Default")
      (node (ref "J1") (pin "A5") (pinfunction "A5_A5") (pintype "bidirectional"))
      (node (ref "R2-USB1") (pin "2") (pinfunction "2_2") (pintype "passive"))
    )
    (net (code "34") (name "Net-(J1-PadB5)") (class "Default")
      (node (ref "J1") (pin "B5") (pinfunction "B5_B5") (pintype "bidirectional"))
      (node (ref "R2-USB") (pin "1") (pinfunction "1_1") (pintype "passive"))
    )
    (net (code "35") (name "Net-(MCP73831-PROG)") (class "Default")
      (node (ref "MCP73831") (pin "5") (pinfunction "PROG_5") (pintype "input"))
      (node (ref "R2_BAT") (pin "2") (pinfunction "2_2") (pintype "passive"))
    )
    (net (code "36") (name "Net-(MCP73831-STAT)") (class "Default")
      (node (ref "MCP73831") (pin "1") (pinfunction "STAT_1") (pintype "output"))
      (node (ref "R1_BAT") (pin "2") (pinfunction "2_2") (pintype "passive"))
    )
    (net (code "37") (name "PREVGH") (class "Default")
      (node (ref "D5") (pin "1") (pinfunction "K_1") (pintype "bidirectional"))
      (node (ref "EPD_C9") (pin "2") (pinfunction "2_2") (pintype "passive"))
      (node (ref "J2") (pin "21") (pinfunction "21_21") (pintype "bidirectional"))
    )
    (net (code "38") (name "PREVGL") (class "Default")
      (node (ref "D4") (pin "2") (pinfunction "A_2") (pintype "bidirectional"))
      (node (ref "EPD_C11") (pin "2") (pinfunction "2_2") (pintype "passive"))
      (node (ref "J2") (pin "23") (pinfunction "23_23") (pintype "bidirectional"))
    )
    (net (code "39") (name "RESE") (class "Default")
      (node (ref "J2") (pin "3") (pinfunction "3_3") (pintype "bidirectional"))
      (node (ref "Q3") (pin "2") (pinfunction "S_2") (pintype "bidirectional"))
      (node (ref "R3") (pin "2") (pinfunction "2_2") (pintype "passive"))
    )
    (net (code "40") (name "RESE'") (class "Default")
      (node (ref "R2") (pin "2") (pinfunction "2_2") (pintype "passive"))
      (node (ref "R3") (pin "1") (pinfunction "1_1") (pintype "passive"))
      (node (ref "SJ1") (pin "2") (pinfunction "2_2") (pintype "passive"))
    )
    (net (code "41") (name "RESET") (class "Default")
      (node (ref "C5") (pin "1") (pinfunction "1_1") (pintype "passive"))
      (node (ref "IC1") (pin "1") (pinfunction "VOUT_1") (pintype "bidirectional"))
      (node (ref "RESET_BUTTON") (pin "3") (pinfunction "3_3") (pintype "passive"))
      (node (ref "RESET_BUTTON") (pin "4") (pinfunction "4_4") (pintype "passive"))
      (node (ref "R_RESET") (pin "1") (pinfunction "1_1") (pintype "passive"))
      (node (ref "U2") (pin "3") (pinfunction "EN_3") (pintype "input"))
    )
    (net (code "42") (name "RTC_RST") (class "Default")
      (node (ref "U2") (pin "16") (pinfunction "IO18_16") (pintype "bidirectional"))
      (node (ref "U3") (pin "4") (pinfunction "~{RST}_4") (pintype "input"))
    )
    (net (code "43") (name "RX") (class "Default")
      (node (ref "RX") (pin "TP") (pinfunction "TP_TP") (pintype "input"))
      (node (ref "U2") (pin "24") (pinfunction "RXD0/GPIO17_24") (pintype "bidirectional"))
    )
    (net (code "44") (name "SCK") (class "Default")
      (node (ref "D10") (pin "2") (pinfunction "2_2") (pintype "passive"))
      (node (ref "J2") (pin "13") (pinfunction "13_13") (pintype "bidirectional"))
      (node (ref "J4") (pin "P5") (pinfunction "CLK_P5") (pintype "bidirectional"))
      (node (ref "R6") (pin "1") (pinfunction "1_1") (pintype "passive"))
      (node (ref "SCK") (pin "TP") (pinfunction "TP_TP") (pintype "input"))
      (node (ref "U1") (pin "6") (pinfunction "CLK_6") (pintype "input"))
      (node (ref "U2") (pin "6") (pinfunction "IO6_6") (pintype "bidirectional"))
    )
    (net (code "45") (name "SCL") (class "Default")
      (node (ref "J3") (pin "4") (pinfunction "4_4") (pintype "passive"))
      (node (ref "R2-PINH") (pin "1") (pinfunction "1_1") (pintype "passive"))
      (node (ref "SENSOR2") (pin "4") (pinfunction "SCK_4") (pintype "input"))
      (node (ref "U2") (pin "20") (pinfunction "IO22_20") (pintype "bidirectional"))
      (node (ref "U3") (pin "16") (pinfunction "SCL_16") (pintype "input"))
      (node (ref "U4") (pin "7") (pinfunction "SCL_7") (pintype "input"))
    )
    (net (code "46") (name "SDA") (class "Default")
      (node (ref "J3") (pin "3") (pinfunction "3_3") (pintype "passive"))
      (node (ref "R1_PINH") (pin "1") (pinfunction "1_1") (pintype "passive"))
      (node (ref "SENSOR2") (pin "3") (pinfunction "SDI_3") (pintype "bidirectional"))
      (node (ref "U2") (pin "19") (pinfunction "IO21_19") (pintype "bidirectional"))
      (node (ref "U3") (pin "15") (pinfunction "SDA_15") (pintype "bidirectional"))
      (node (ref "U4") (pin "8") (pinfunction "SDA_8") (pintype "bidirectional"))
    )
    (net (code "47") (name "SRC") (class "Default")
      (node (ref "C4") (pin "2") (pinfunction "2_2") (pintype "passive"))
      (node (ref "D5") (pin "2") (pinfunction "A_2") (pintype "bidirectional"))
      (node (ref "L1") (pin "1") (pinfunction "1_1") (pintype "passive"))
      (node (ref "Q3") (pin "3") (pinfunction "D_3") (pintype "bidirectional"))
    )
    (net (code "48") (name "SS_SD") (class "Default")
      (node (ref "D8") (pin "2") (pinfunction "2_2") (pintype "passive"))
      (node (ref "J4") (pin "P2") (pinfunction "CD/DAT3_P2") (pintype "bidirectional"))
      (node (ref "R10") (pin "1") (pinfunction "1_1") (pintype "passive"))
      (node (ref "U2") (pin "4") (pinfunction "IO4_4") (pintype "bidirectional"))
    )
    (net (code "49") (name "TX") (class "Default")
      (node (ref "TX") (pin "TP") (pinfunction "TP_TP") (pintype "input"))
      (node (ref "U2") (pin "25") (pinfunction "TXD0/GPIO16_25") (pintype "bidirectional"))
    )
    (net (code "50") (name "USB_D+") (class "Default")
      (node (ref "D1") (pin "1") (pinfunction "I/O1_1_1") (pintype "bidirectional"))
      (node (ref "U2") (pin "14") (pinfunction "IO13_14") (pintype "bidirectional"))
    )
    (net (code "51") (name "USB_D-") (class "Default")
      (node (ref "D1") (pin "3") (pinfunction "I/O2_1_3") (pintype "bidirectional"))
      (node (ref "U2") (pin "13") (pinfunction "IO12_13") (pintype "bidirectional"))
    )
    (net (code "52") (name "VBAT") (class "Default")
      (node (ref "C2_BAT") (pin "1") (pinfunction "1_1") (pintype "passive"))
      (node (ref "MCP73831") (pin "3") (pinfunction "VBAT_3") (pintype "power_in"))
      (node (ref "Q1") (pin "3") (pinfunction "D_3") (pintype "bidirectional"))
      (node (ref "U4") (pin "2") (pinfunction "CELL_2") (pintype "power_in"))
      (node (ref "U4") (pin "3") (pinfunction "VDD_3") (pintype "power_in"))
      (node (ref "VBAT") (pin "TP") (pinfunction "TP_TP") (pintype "input"))
    )
    (net (code "53") (name "VBUS") (class "Default")
      (node (ref "C1_BAT") (pin "1") (pinfunction "1_1") (pintype "passive"))
      (node (ref "C4_USB") (pin "1") (pinfunction "1_1") (pintype "passive"))
      (node (ref "C5_USB") (pin "1") (pinfunction "1_1") (pintype "passive"))
      (node (ref "CHG_LED") (pin "A") (pinfunction "A_A") (pintype "passive"))
      (node (ref "D1") (pin "5") (pinfunction "VBUS_5") (pintype "bidirectional"))
      (node (ref "D2") (pin "2") (pinfunction "ANODE_2") (pintype "bidirectional"))
      (node (ref "MCP73831") (pin "4") (pinfunction "VIN_4") (pintype "power_in"))
      (node (ref "PFMF.050.1") (pin "2") (pinfunction "2_2") (pintype "passive"))
      (node (ref "Q1") (pin "1") (pinfunction "G_1") (pintype "bidirectional"))
      (node (ref "R1_PWRUSB") (pin "2") (pinfunction "2_2") (pintype "passive"))
      (node (ref "VBUS") (pin "TP") (pinfunction "TP_TP") (pintype "input"))
    )
    (net (code "54") (name "VRTC") (class "Default")
      (node (ref "C10_SUPERCAP") (pin "2") (pinfunction "2_2") (pintype "passive"))
      (node (ref "C8") (pin "1") (pinfunction "1_1") (pintype "passive"))
      (node (ref "R_CAPACITOR") (pin "2") (pinfunction "2_2") (pintype "passive"))
      (node (ref "U3") (pin "14") (pinfunction "VBAT_14") (pintype "power_in"))
    )
    (net (code "55") (name "VUSB") (class "Default")
      (node (ref "J1") (pin "A4") (pinfunction "A4_A4") (pintype "bidirectional"))
      (node (ref "J1") (pin "A9") (pinfunction "A9_A9") (pintype "bidirectional"))
      (node (ref "J1") (pin "B4") (pinfunction "B4_B4") (pintype "bidirectional"))
      (node (ref "J1") (pin "B9") (pinfunction "B9_B9") (pintype "bidirectional"))
      (node (ref "PFMF.050.1") (pin "1") (pinfunction "1_1") (pintype "passive"))
    )
    (net (code "56") (name "unconnected-(IC1-NC-Pad4)") (class "Default")
      (node (ref "IC1") (pin "4") (pinfunction "NC_4") (pintype "no_connect"))
    )
    (net (code "57") (name "unconnected-(IC4-NC-Pad4)") (class "Default")
      (node (ref "IC4") (pin "4") (pinfunction "NC_4") (pintype "no_connect"))
    )
    (net (code "58") (name "unconnected-(J1-PadA8)") (class "Default")
      (node (ref "J1") (pin "A8") (pinfunction "A8_A8") (pintype "bidirectional"))
    )
    (net (code "59") (name "unconnected-(J1-PadB8)") (class "Default")
      (node (ref "J1") (pin "B8") (pinfunction "B8_B8") (pintype "bidirectional"))
    )
    (net (code "60") (name "unconnected-(J2-Pad1)") (class "Default")
      (node (ref "J2") (pin "1") (pinfunction "1_1") (pintype "bidirectional"))
    )
    (net (code "61") (name "unconnected-(J2-Pad6)") (class "Default")
      (node (ref "J2") (pin "6") (pinfunction "6_6") (pintype "bidirectional"))
    )
    (net (code "62") (name "unconnected-(J2-Pad7)") (class "Default")
      (node (ref "J2") (pin "7") (pinfunction "7_7") (pintype "bidirectional"))
    )
    (net (code "63") (name "unconnected-(J4-DAT1-PadP8)") (class "Default")
      (node (ref "J4") (pin "P8") (pinfunction "DAT1_P8") (pintype "bidirectional"))
    )
    (net (code "64") (name "unconnected-(J4-DAT2-PadP1)") (class "Default")
      (node (ref "J4") (pin "P1") (pinfunction "DAT2_P1") (pintype "bidirectional"))
    )
    (net (code "65") (name "unconnected-(J4-DETECTION_1-PadS1)") (class "Default")
      (node (ref "J4") (pin "S1") (pinfunction "DETECTION_1_S1") (pintype "bidirectional"))
    )
    (net (code "66") (name "unconnected-(J4-DETECTION_2-PadS2)") (class "Default")
      (node (ref "J4") (pin "S2") (pinfunction "DETECTION_2_S2") (pintype "bidirectional"))
    )
    (net (code "67") (name "unconnected-(U2-NC-Pad22)") (class "Default")
      (node (ref "U2") (pin "22") (pinfunction "NC_22") (pintype "no_connect"))
    )
    (net (code "68") (name "unconnected-(U4-~{ALERT}-Pad5)") (class "Default")
      (node (ref "U4") (pin "5") (pinfunction "~{ALERT}_5") (pintype "output"))
    )
  )
)
